# untitled.net
KiCad netlist of a schematic drawn in EAGLE
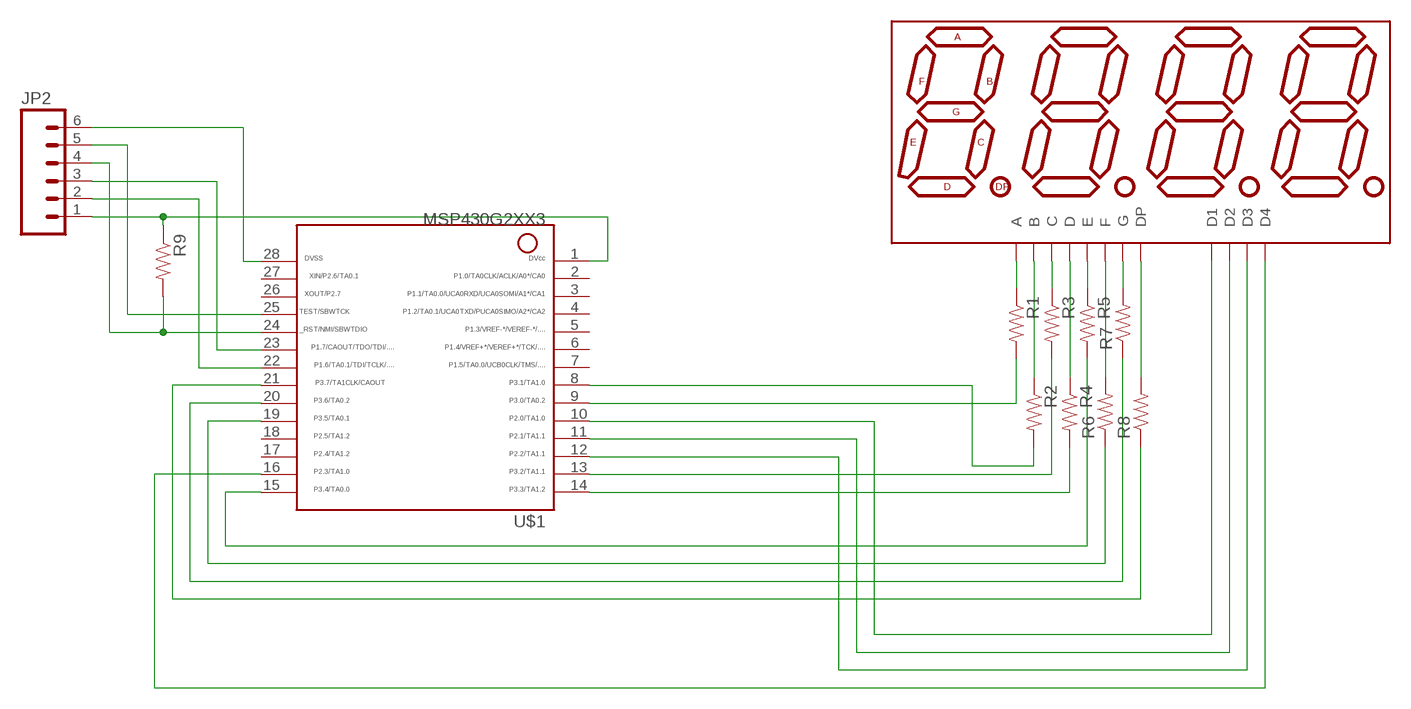
[diagram p0: schematic, sheet 1]

(export (version "E")
  (design (tool "Eeschema 10.0.6"))
  (components
    (comp (ref "JP2")
      (value "M06LOCK")
      (footprint "eagle-import:1X06_LOCK")
      (libsource (lib "eagle-import") (part "M06LOCK"))
    )
    (comp (ref "R1")
      (value "RESISTOR1206")
      (footprint "eagle-import:1206")
      (libsource (lib "eagle-import") (part "RESISTOR1206"))
    )
    (comp (ref "R2")
      (value "RESISTOR1206")
      (footprint "eagle-import:1206")
      (libsource (lib "eagle-import") (part "RESISTOR1206"))
    )
    (comp (ref "R3")
      (value "RESISTOR1206")
      (footprint "eagle-import:1206")
      (libsource (lib "eagle-import") (part "RESISTOR1206"))
    )
    (comp (ref "R4")
      (value "RESISTOR1206")
      (footprint "eagle-import:1206")
      (libsource (lib "eagle-import") (part "RESISTOR1206"))
    )
    (comp (ref "R5")
      (value "RESISTOR1206")
      (footprint "eagle-import:1206")
      (libsource (lib "eagle-import") (part "RESISTOR1206"))
    )
    (comp (ref "R6")
      (value "RESISTOR1206")
      (footprint "eagle-import:1206")
      (libsource (lib "eagle-import") (part "RESISTOR1206"))
    )
    (comp (ref "R7")
      (value "RESISTOR1206")
      (footprint "eagle-import:1206")
      (libsource (lib "eagle-import") (part "RESISTOR1206"))
    )
    (comp (ref "R8")
      (value "RESISTOR1206")
      (footprint "eagle-import:1206")
      (libsource (lib "eagle-import") (part "RESISTOR1206"))
    )
    (comp (ref "R9")
      (value "RESISTOR1206")
      (footprint "eagle-import:1206")
      (libsource (lib "eagle-import") (part "RESISTOR1206"))
    )
    (comp (ref "U$1")
      (value "G2XX3---PW28")
      (footprint "eagle-import:PW28")
      (libsource (lib "eagle-import") (part "G2XX3---PW28"))
    )
    (comp (ref "U$2")
      (value "7-SEGMENT-4DIGIT-COUNTERPTH")
      (footprint "eagle-import:7-SEGMENT-4DIGIT-COUNTER")
      (libsource (lib "eagle-import") (part "7-SEGMENT-4DIGIT-COUNTERPTH"))
    )
  )
  (nets
    (net (code "1") (name "Net-(JP2-Pad1)") (class "Default")
      (node (ref "JP2") (pin "1") (pinfunction "1_1") (pintype "passive"))
      (node (ref "R9") (pin "1") (pinfunction "1_1") (pintype "passive"))
      (node (ref "U$1") (pin "1") (pinfunction "1_1") (pintype "bidirectional"))
    )
    (net (code "2") (name "Net-(JP2-Pad2)") (class "Default")
      (node (ref "JP2") (pin "2") (pinfunction "2_2") (pintype "passive"))
      (node (ref "U$1") (pin "22") (pinfunction "22_22") (pintype "bidirectional"))
    )
    (net (code "3") (name "Net-(JP2-Pad3)") (class "Default")
      (node (ref "JP2") (pin "3") (pinfunction "3_3") (pintype "passive"))
      (node (ref "U$1") (pin "23") (pinfunction "23_23") (pintype "bidirectional"))
    )
    (net (code "4") (name "Net-(JP2-Pad4)") (class "Default")
      (node (ref "JP2") (pin "4") (pinfunction "4_4") (pintype "passive"))
      (node (ref "R9") (pin "2") (pinfunction "2_2") (pintype "passive"))
      (node (ref "U$1") (pin "24") (pinfunction "24_24") (pintype "bidirectional"))
    )
    (net (code "5") (name "Net-(JP2-Pad5)") (class "Default")
      (node (ref "JP2") (pin "5") (pinfunction "5_5") (pintype "passive"))
      (node (ref "U$1") (pin "25") (pinfunction "25_25") (pintype "bidirectional"))
    )
    (net (code "6") (name "Net-(JP2-Pad6)") (class "Default")
      (node (ref "JP2") (pin "6") (pinfunction "6_6") (pintype "passive"))
      (node (ref "U$1") (pin "28") (pinfunction "28_28") (pintype "bidirectional"))
    )
    (net (code "7") (name "Net-(R1-Pad2)") (class "Default")
      (node (ref "R1") (pin "2") (pinfunction "2_2") (pintype "passive"))
      (node (ref "U$1") (pin "9") (pinfunction "9_9") (pintype "bidirectional"))
    )
    (net (code "8") (name "Net-(R2-Pad2)") (class "Default")
      (node (ref "R2") (pin "2") (pinfunction "2_2") (pintype "passive"))
      (node (ref "U$1") (pin "8") (pinfunction "8_8") (pintype "bidirectional"))
    )
    (net (code "9") (name "Net-(R3-Pad2)") (class "Default")
      (node (ref "R3") (pin "2") (pinfunction "2_2") (pintype "passive"))
      (node (ref "U$1") (pin "13") (pinfunction "13_13") (pintype "bidirectional"))
    )
    (net (code "10") (name "Net-(R4-Pad2)") (class "Default")
      (node (ref "R4") (pin "2") (pinfunction "2_2") (pintype "passive"))
      (node (ref "U$1") (pin "14") (pinfunction "14_14") (pintype "bidirectional"))
    )
    (net (code "11") (name "Net-(R5-Pad2)") (class "Default")
      (node (ref "R5") (pin "2") (pinfunction "2_2") (pintype "passive"))
      (node (ref "U$1") (pin "15") (pinfunction "15_15") (pintype "bidirectional"))
    )
    (net (code "12") (name "Net-(R6-Pad1)") (class "Default")
      (node (ref "R6") (pin "1") (pinfunction "1_1") (pintype "passive"))
      (node (ref "U$1") (pin "19") (pinfunction "19_19") (pintype "bidirectional"))
    )
    (net (code "13") (name "Net-(R7-Pad1)") (class "Default")
      (node (ref "R7") (pin "1") (pinfunction "1_1") (pintype "passive"))
      (node (ref "U$1") (pin "20") (pinfunction "20_20") (pintype "bidirectional"))
    )
    (net (code "14") (name "Net-(R8-Pad1)") (class "Default")
      (node (ref "R8") (pin "1") (pinfunction "1_1") (pintype "passive"))
      (node (ref "U$1") (pin "21") (pinfunction "21_21") (pintype "bidirectional"))
    )
    (net (code "15") (name "Net-(U$2-A)") (class "Default")
      (node (ref "R1") (pin "1") (pinfunction "1_1") (pintype "passive"))
      (node (ref "U$2") (pin "11") (pinfunction "A_11") (pintype "bidirectional"))
    )
    (net (code "16") (name "Net-(U$2-B)") (class "Default")
      (node (ref "R2") (pin "1") (pinfunction "1_1") (pintype "passive"))
      (node (ref "U$2") (pin "7") (pinfunction "B_7") (pintype "bidirectional"))
    )
    (net (code "17") (name "Net-(U$2-C)") (class "Default")
      (node (ref "R3") (pin "1") (pinfunction "1_1") (pintype "passive"))
      (node (ref "U$2") (pin "4") (pinfunction "C_4") (pintype "bidirectional"))
    )
    (net (code "18") (name "Net-(U$2-D)") (class "Default")
      (node (ref "R4") (pin "1") (pinfunction "1_1") (pintype "passive"))
      (node (ref "U$2") (pin "2") (pinfunction "D_2") (pintype "bidirectional"))
    )
    (net (code "19") (name "Net-(U$2-D1)") (class "Default")
      (node (ref "U$1") (pin "10") (pinfunction "10_10") (pintype "bidirectional"))
      (node (ref "U$2") (pin "12") (pinfunction "D1_12") (pintype "bidirectional"))
    )
    (net (code "20") (name "Net-(U$2-D2)") (class "Default")
      (node (ref "U$1") (pin "11") (pinfunction "11_11") (pintype "bidirectional"))
      (node (ref "U$2") (pin "9") (pinfunction "D2_9") (pintype "bidirectional"))
    )
    (net (code "21") (name "Net-(U$2-D3)") (class "Default")
      (node (ref "U$1") (pin "12") (pinfunction "12_12") (pintype "bidirectional"))
      (node (ref "U$2") (pin "8") (pinfunction "D3_8") (pintype "bidirectional"))
    )
    (net (code "22") (name "Net-(U$2-D4)") (class "Default")
      (node (ref "U$1") (pin "16") (pinfunction "16_16") (pintype "bidirectional"))
      (node (ref "U$2") (pin "6") (pinfunction "D4_6") (pintype "bidirectional"))
    )
    (net (code "23") (name "Net-(U$2-DP)") (class "Default")
      (node (ref "R8") (pin "2") (pinfunction "2_2") (pintype "passive"))
      (node (ref "U$2") (pin "3") (pinfunction "DP_3") (pintype "bidirectional"))
    )
    (net (code "24") (name "Net-(U$2-E)") (class "Default")
      (node (ref "R5") (pin "1") (pinfunction "1_1") (pintype "passive"))
      (node (ref "U$2") (pin "1") (pinfunction "E_1") (pintype "bidirectional"))
    )
    (net (code "25") (name "Net-(U$2-F)") (class "Default")
      (node (ref "R6") (pin "2") (pinfunction "2_2") (pintype "passive"))
      (node (ref "U$2") (pin "10") (pinfunction "F_10") (pintype "bidirectional"))
    )
    (net (code "26") (name "Net-(U$2-G)") (class "Default")
      (node (ref "R7") (pin "2") (pinfunction "2_2") (pintype "passive"))
      (node (ref "U$2") (pin "5") (pinfunction "G_5") (pintype "bidirectional"))
    )
    (net (code "27") (name "unconnected-(U$1-Pad2)") (class "Default")
      (node (ref "U$1") (pin "2") (pinfunction "2_2") (pintype "bidirectional"))
    )
    (net (code "28") (name "unconnected-(U$1-Pad3)") (class "Default")
      (node (ref "U$1") (pin "3") (pinfunction "3_3") (pintype "bidirectional"))
    )
    (net (code "29") (name "unconnected-(U$1-Pad4)") (class "Default")
      (node (ref "U$1") (pin "4") (pinfunction "4_4") (pintype "bidirectional"))
    )
    (net (code "30") (name "unconnected-(U$1-Pad5)") (class "Default")
      (node (ref "U$1") (pin "5") (pinfunction "5_5") (pintype "bidirectional"))
    )
    (net (code "31") (name "unconnected-(U$1-Pad6)") (class "Default")
      (node (ref "U$1") (pin "6") (pinfunction "6_6") (pintype "bidirectional"))
    )
    (net (code "32") (name "unconnected-(U$1-Pad7)") (class "Default")
      (node (ref "U$1") (pin "7") (pinfunction "7_7") (pintype "bidirectional"))
    )
    (net (code "33") (name "unconnected-(U$1-Pad17)") (class "Default")
      (node (ref "U$1") (pin "17") (pinfunction "17_17") (pintype "bidirectional"))
    )
    (net (code "34") (name "unconnected-(U$1-Pad18)") (class "Default")
      (node (ref "U$1") (pin "18") (pinfunction "18_18") (pintype "bidirectional"))
    )
    (net (code "35") (name "unconnected-(U$1-Pad26)") (class "Default")
      (node (ref "U$1") (pin "26") (pinfunction "26_26") (pintype "bidirectional"))
    )
    (net (code "36") (name "unconnected-(U$1-Pad27)") (class "Default")
      (node (ref "U$1") (pin "27") (pinfunction "27_27") (pintype "bidirectional"))
    )
  )
)
